# Combat.net
KiCad netlist of a schematic drawn in EAGLE
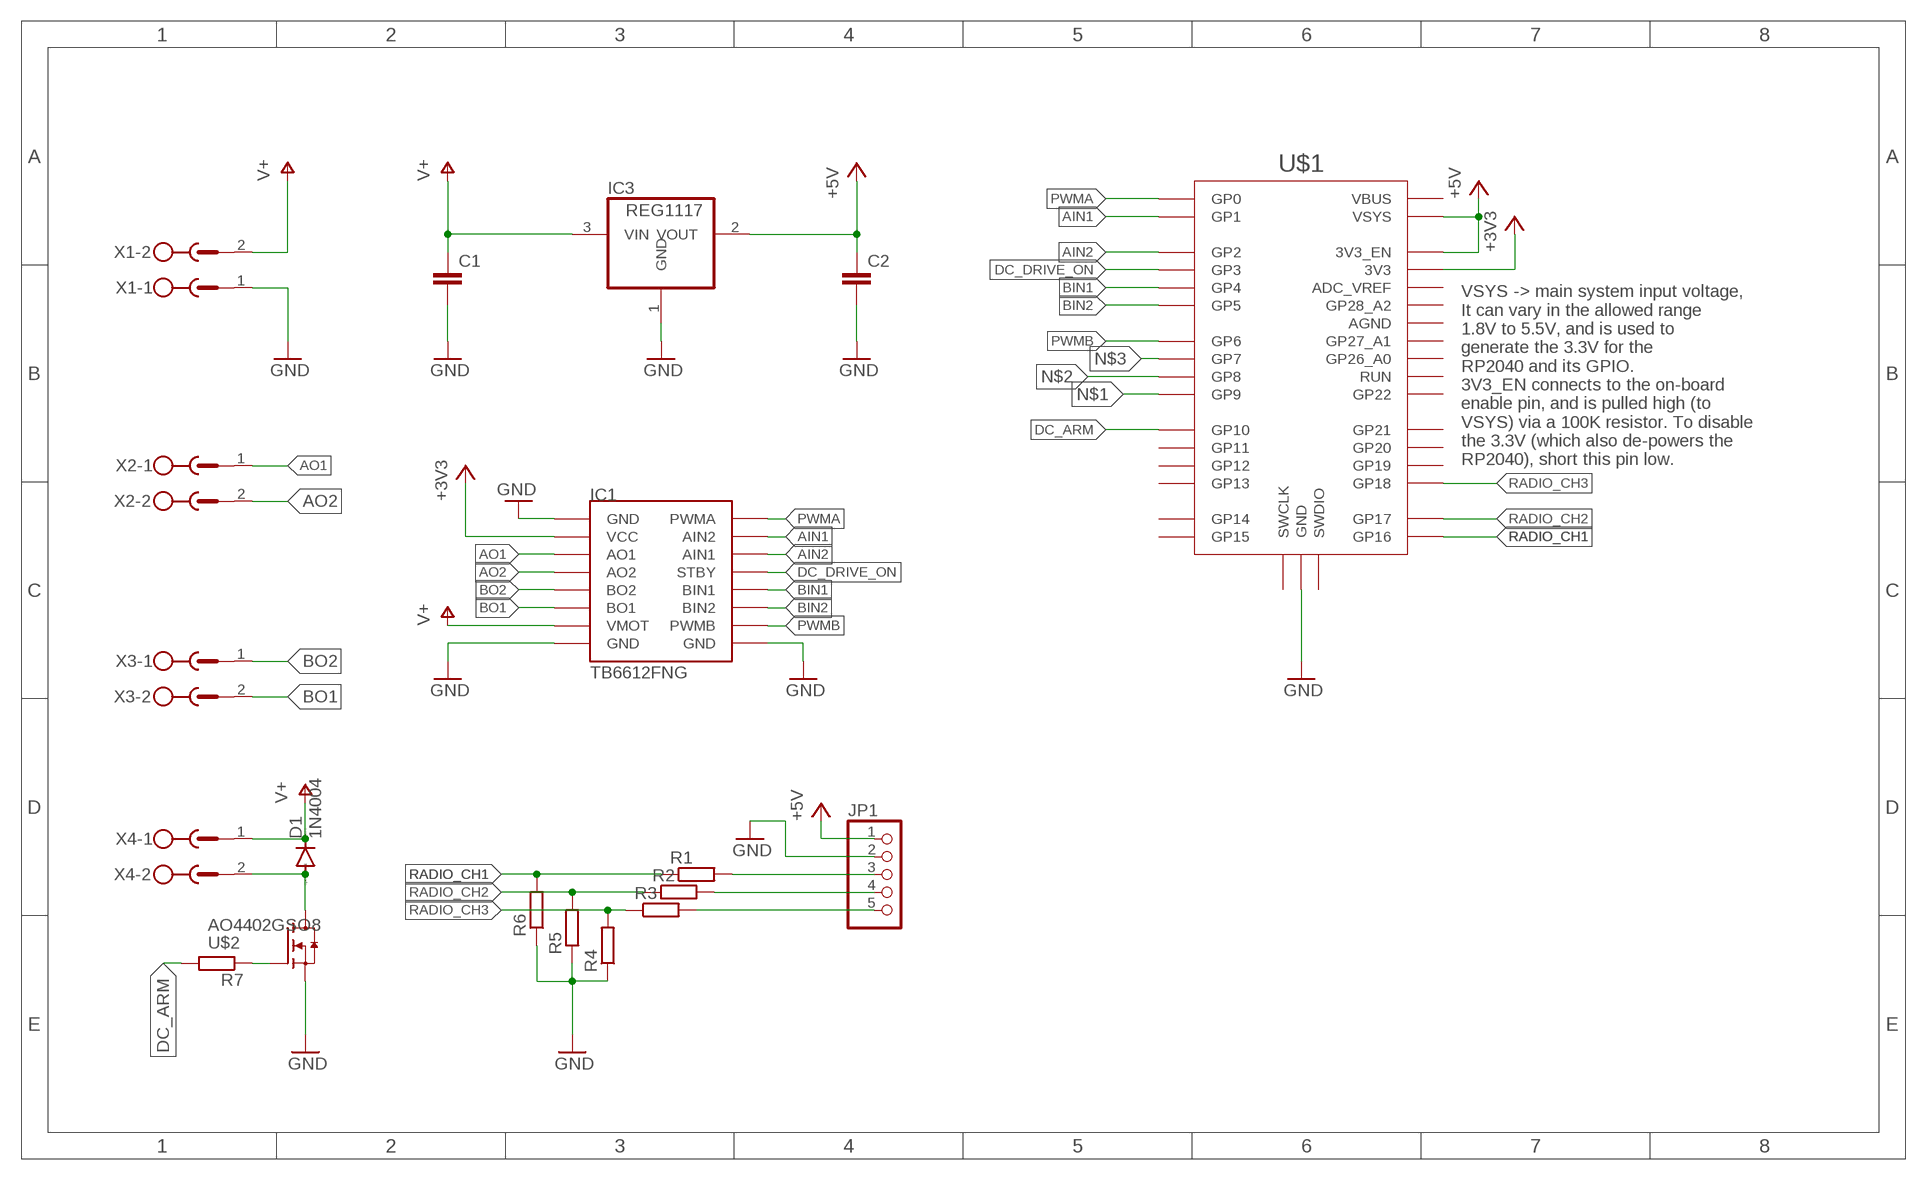
[diagram p0: schematic, sheet 1]

(export (version "E")
  (design (tool "Eeschema 10.0.6"))
  (components
    (comp (ref "C1")
      (value "C-EUC1206")
      (footprint "eagle-import:C1206")
      (libsource (lib "eagle-import") (part "C-EUC1206"))
    )
    (comp (ref "C2")
      (value "C-EUC1206")
      (footprint "eagle-import:C1206")
      (libsource (lib "eagle-import") (part "C-EUC1206"))
    )
    (comp (ref "D1")
      (value "1N4004")
      (footprint "eagle-import:DO41-10")
      (libsource (lib "eagle-import") (part "1N4004"))
    )
    (comp (ref "IC1")
      (value "MODUL_POLOLU")
      (footprint "eagle-import:MODUL_POLOLU")
      (libsource (lib "eagle-import") (part "MODUL_POLOLU"))
    )
    (comp (ref "IC3")
      (value "REG1117")
      (footprint "eagle-import:SOT223")
      (libsource (lib "eagle-import") (part "REG1117"))
    )
    (comp (ref "JP1")
      (value "PINHD-1X5")
      (footprint "eagle-import:1X05")
      (libsource (lib "eagle-import") (part "PINHD-1X5"))
    )
    (comp (ref "R1")
      (value "R-EU_R1206")
      (footprint "eagle-import:R1206")
      (libsource (lib "eagle-import") (part "R-EU_R1206"))
    )
    (comp (ref "R2")
      (value "R-EU_R1206")
      (footprint "eagle-import:R1206")
      (libsource (lib "eagle-import") (part "R-EU_R1206"))
    )
    (comp (ref "R3")
      (value "R-EU_R1206")
      (footprint "eagle-import:R1206")
      (libsource (lib "eagle-import") (part "R-EU_R1206"))
    )
    (comp (ref "R4")
      (value "R-EU_R1206")
      (footprint "eagle-import:R1206")
      (libsource (lib "eagle-import") (part "R-EU_R1206"))
    )
    (comp (ref "R5")
      (value "R-EU_0204/7")
      (footprint "eagle-import:0204_7")
      (libsource (lib "eagle-import") (part "R-EU_0204/7"))
    )
    (comp (ref "R6")
      (value "R-EU_R1206")
      (footprint "eagle-import:R1206")
      (libsource (lib "eagle-import") (part "R-EU_R1206"))
    )
    (comp (ref "R7")
      (value "R-EU_R1206")
      (footprint "eagle-import:R1206")
      (libsource (lib "eagle-import") (part "R-EU_R1206"))
    )
    (comp (ref "U$1")
      (value "RPI_PICO-TH")
      (footprint "eagle-import:RPI_PICO_TH")
      (libsource (lib "eagle-import") (part "RPI_PICO-TH"))
    )
    (comp (ref "U$2")
      (value "AO4402GSO8")
      (footprint "eagle-import:SO8")
      (libsource (lib "eagle-import") (part "AO4402GSO8"))
    )
    (comp (ref "X1")
      (value "MSTBV2")
      (footprint "eagle-import:MSTBV2")
      (libsource (lib "eagle-import") (part "MSTBV2"))
    )
    (comp (ref "X2")
      (value "MSTBV2")
      (footprint "eagle-import:MSTBV2")
      (libsource (lib "eagle-import") (part "MSTBV2"))
    )
    (comp (ref "X3")
      (value "MSTBV2")
      (footprint "eagle-import:MSTBV2")
      (libsource (lib "eagle-import") (part "MSTBV2"))
    )
    (comp (ref "X4")
      (value "MSTBV2")
      (footprint "eagle-import:MSTBV2")
      (libsource (lib "eagle-import") (part "MSTBV2"))
    )
  )
  (nets
    (net (code "1") (name "+3V3") (class "Default")
      (node (ref "IC1") (pin "VCC") (pinfunction "VCC_VCC") (pintype "bidirectional"))
      (node (ref "U$1") (pin "3V3") (pinfunction "3V3_3V3") (pintype "bidirectional"))
    )
    (net (code "2") (name "+5V") (class "Default")
      (node (ref "C2") (pin "1") (pinfunction "1_1") (pintype "passive"))
      (node (ref "IC3") (pin "2") (pinfunction "VOUT_2") (pintype "output"))
      (node (ref "JP1") (pin "1") (pinfunction "1_1") (pintype "passive"))
      (node (ref "U$1") (pin "3V3_EN") (pinfunction "3V3_EN_3V3_EN") (pintype "bidirectional"))
      (node (ref "U$1") (pin "VSYS") (pinfunction "VSYS_VSYS") (pintype "bidirectional"))
    )
    (net (code "3") (name "AIN1") (class "Default")
      (node (ref "IC1") (pin "AIN2") (pinfunction "AIN2_AIN2") (pintype "bidirectional"))
      (node (ref "U$1") (pin "GP1") (pinfunction "GP1_GP1") (pintype "bidirectional"))
    )
    (net (code "4") (name "AIN2") (class "Default")
      (node (ref "IC1") (pin "AIN1") (pinfunction "AIN1_AIN1") (pintype "bidirectional"))
      (node (ref "U$1") (pin "GP2") (pinfunction "GP2_GP2") (pintype "bidirectional"))
    )
    (net (code "5") (name "AO1") (class "Default")
      (node (ref "IC1") (pin "AO1") (pinfunction "AO1_AO1") (pintype "bidirectional"))
      (node (ref "X2") (pin "1") (pinfunction "SK_1") (pintype "passive"))
    )
    (net (code "6") (name "AO2") (class "Default")
      (node (ref "IC1") (pin "A02") (pinfunction "AO2_A02") (pintype "bidirectional"))
      (node (ref "X2") (pin "2") (pinfunction "SK_2") (pintype "passive"))
    )
    (net (code "7") (name "BIN1") (class "Default")
      (node (ref "IC1") (pin "BIN1") (pinfunction "BIN1_BIN1") (pintype "bidirectional"))
      (node (ref "U$1") (pin "GP4") (pinfunction "GP4_GP4") (pintype "bidirectional"))
    )
    (net (code "8") (name "BIN2") (class "Default")
      (node (ref "IC1") (pin "BIN2") (pinfunction "BIN2_BIN2") (pintype "bidirectional"))
      (node (ref "U$1") (pin "GP5") (pinfunction "GP5_GP5") (pintype "bidirectional"))
    )
    (net (code "9") (name "BO1") (class "Default")
      (node (ref "IC1") (pin "BO1") (pinfunction "BO1_BO1") (pintype "bidirectional"))
      (node (ref "X3") (pin "2") (pinfunction "SK_2") (pintype "passive"))
    )
    (net (code "10") (name "BO2") (class "Default")
      (node (ref "IC1") (pin "BO2") (pinfunction "BO2_BO2") (pintype "bidirectional"))
      (node (ref "X3") (pin "1") (pinfunction "SK_1") (pintype "passive"))
    )
    (net (code "11") (name "DC_ARM") (class "Default")
      (node (ref "R7") (pin "2") (pinfunction "2_2") (pintype "passive"))
      (node (ref "U$1") (pin "GP10") (pinfunction "GP10_GP10") (pintype "bidirectional"))
    )
    (net (code "12") (name "DC_DRIVE_ON") (class "Default")
      (node (ref "IC1") (pin "STBY") (pinfunction "STBY_STBY") (pintype "bidirectional"))
      (node (ref "U$1") (pin "GP3") (pinfunction "GP3_GP3") (pintype "bidirectional"))
    )
    (net (code "13") (name "GND") (class "Default")
      (node (ref "C1") (pin "2") (pinfunction "2_2") (pintype "passive"))
      (node (ref "C2") (pin "2") (pinfunction "2_2") (pintype "passive"))
      (node (ref "IC1") (pin "GND1") (pinfunction "GND_GND1") (pintype "bidirectional"))
      (node (ref "IC1") (pin "GND2") (pinfunction "GND_GND2") (pintype "bidirectional"))
      (node (ref "IC1") (pin "GND3") (pinfunction "GND_GND3") (pintype "bidirectional"))
      (node (ref "IC3") (pin "1") (pinfunction "GND_1") (pintype "power_in"))
      (node (ref "JP1") (pin "2") (pinfunction "2_2") (pintype "passive"))
      (node (ref "R4") (pin "1") (pinfunction "1_1") (pintype "passive"))
      (node (ref "R5") (pin "1") (pinfunction "1_1") (pintype "passive"))
      (node (ref "R6") (pin "1") (pinfunction "1_1") (pintype "passive"))
      (node (ref "U$1") (pin "GND@1") (pinfunction "GND_GND@1") (pintype "bidirectional"))
      (node (ref "U$1") (pin "GND@2") (pinfunction "GND_GND@2") (pintype "bidirectional"))
      (node (ref "U$1") (pin "GND@3") (pinfunction "GND_GND@3") (pintype "bidirectional"))
      (node (ref "U$1") (pin "GND@4") (pinfunction "GND_GND@4") (pintype "bidirectional"))
      (node (ref "U$1") (pin "GND@5") (pinfunction "GND_GND@5") (pintype "bidirectional"))
      (node (ref "U$1") (pin "GND@6") (pinfunction "GND_GND@6") (pintype "bidirectional"))
      (node (ref "U$1") (pin "GND@7") (pinfunction "GND_GND@7") (pintype "bidirectional"))
      (node (ref "U$1") (pin "GND@8") (pinfunction "GND_GND@8") (pintype "bidirectional"))
      (node (ref "U$2") (pin "1") (pinfunction "S_1") (pintype "passive"))
      (node (ref "U$2") (pin "2") (pinfunction "S_2") (pintype "passive"))
      (node (ref "U$2") (pin "3") (pinfunction "S_3") (pintype "passive"))
      (node (ref "X1") (pin "1") (pinfunction "SK_1") (pintype "passive"))
    )
    (net (code "14") (name "N$1") (class "Default")
      (node (ref "JP1") (pin "3") (pinfunction "3_3") (pintype "passive"))
      (node (ref "R1") (pin "2") (pinfunction "2_2") (pintype "passive"))
      (node (ref "U$1") (pin "GP9") (pinfunction "GP9_GP9") (pintype "bidirectional"))
    )
    (net (code "15") (name "N$2") (class "Default")
      (node (ref "JP1") (pin "4") (pinfunction "4_4") (pintype "passive"))
      (node (ref "R2") (pin "2") (pinfunction "2_2") (pintype "passive"))
      (node (ref "U$1") (pin "GP8") (pinfunction "GP8_GP8") (pintype "bidirectional"))
    )
    (net (code "16") (name "N$3") (class "Default")
      (node (ref "JP1") (pin "5") (pinfunction "5_5") (pintype "passive"))
      (node (ref "R3") (pin "2") (pinfunction "2_2") (pintype "passive"))
      (node (ref "U$1") (pin "GP7") (pinfunction "GP7_GP7") (pintype "bidirectional"))
    )
    (net (code "17") (name "Net-(U$2-G)") (class "Default")
      (node (ref "R7") (pin "1") (pinfunction "1_1") (pintype "passive"))
      (node (ref "U$2") (pin "4") (pinfunction "G_4") (pintype "passive"))
    )
    (net (code "18") (name "Net-(X4B-SK)") (class "Default")
      (node (ref "D1") (pin "A") (pinfunction "A_A") (pintype "passive"))
      (node (ref "U$2") (pin "5") (pinfunction "D_5") (pintype "passive"))
      (node (ref "U$2") (pin "6") (pinfunction "D_6") (pintype "passive"))
      (node (ref "U$2") (pin "7") (pinfunction "D_7") (pintype "passive"))
      (node (ref "U$2") (pin "8") (pinfunction "D_8") (pintype "passive"))
      (node (ref "X4") (pin "2") (pinfunction "SK_2") (pintype "passive"))
    )
    (net (code "19") (name "PWMA") (class "Default")
      (node (ref "IC1") (pin "PWMA") (pinfunction "PWMA_PWMA") (pintype "bidirectional"))
      (node (ref "U$1") (pin "GP0") (pinfunction "GP0_GP0") (pintype "bidirectional"))
    )
    (net (code "20") (name "PWMB") (class "Default")
      (node (ref "IC1") (pin "PWMB") (pinfunction "PWMB_PWMB") (pintype "bidirectional"))
      (node (ref "U$1") (pin "GP6") (pinfunction "GP6_GP6") (pintype "bidirectional"))
    )
    (net (code "21") (name "RADIO_CH1") (class "Default")
      (node (ref "R1") (pin "1") (pinfunction "1_1") (pintype "passive"))
      (node (ref "R6") (pin "2") (pinfunction "2_2") (pintype "passive"))
      (node (ref "U$1") (pin "GP16") (pinfunction "GP16_GP16") (pintype "bidirectional"))
    )
    (net (code "22") (name "RADIO_CH2") (class "Default")
      (node (ref "R2") (pin "1") (pinfunction "1_1") (pintype "passive"))
      (node (ref "R5") (pin "2") (pinfunction "2_2") (pintype "passive"))
      (node (ref "U$1") (pin "GP17") (pinfunction "GP17_GP17") (pintype "bidirectional"))
    )
    (net (code "23") (name "RADIO_CH3") (class "Default")
      (node (ref "R3") (pin "1") (pinfunction "1_1") (pintype "passive"))
      (node (ref "R4") (pin "2") (pinfunction "2_2") (pintype "passive"))
      (node (ref "U$1") (pin "GP18") (pinfunction "GP18_GP18") (pintype "bidirectional"))
    )
    (net (code "24") (name "V+") (class "Default")
      (node (ref "C1") (pin "1") (pinfunction "1_1") (pintype "passive"))
      (node (ref "D1") (pin "C") (pinfunction "C_C") (pintype "passive"))
      (node (ref "IC1") (pin "VMOT") (pinfunction "VMOT_VMOT") (pintype "bidirectional"))
      (node (ref "IC3") (pin "3") (pinfunction "VIN_3") (pintype "input"))
      (node (ref "X1") (pin "2") (pinfunction "SK_2") (pintype "passive"))
      (node (ref "X4") (pin "1") (pinfunction "SK_1") (pintype "passive"))
    )
    (net (code "25") (name "unconnected-(U$1-PadADC_VREF)") (class "Default")
      (node (ref "U$1") (pin "ADC_VREF") (pinfunction "ADC_VREF_ADC_VREF") (pintype "bidirectional"))
    )
    (net (code "26") (name "unconnected-(U$1-PadAGND)") (class "Default")
      (node (ref "U$1") (pin "AGND") (pinfunction "AGND_AGND") (pintype "bidirectional"))
    )
    (net (code "27") (name "unconnected-(U$1-PadGP11)") (class "Default")
      (node (ref "U$1") (pin "GP11") (pinfunction "GP11_GP11") (pintype "bidirectional"))
    )
    (net (code "28") (name "unconnected-(U$1-PadGP12)") (class "Default")
      (node (ref "U$1") (pin "GP12") (pinfunction "GP12_GP12") (pintype "bidirectional"))
    )
    (net (code "29") (name "unconnected-(U$1-PadGP13)") (class "Default")
      (node (ref "U$1") (pin "GP13") (pinfunction "GP13_GP13") (pintype "bidirectional"))
    )
    (net (code "30") (name "unconnected-(U$1-PadGP14)") (class "Default")
      (node (ref "U$1") (pin "GP14") (pinfunction "GP14_GP14") (pintype "bidirectional"))
    )
    (net (code "31") (name "unconnected-(U$1-PadGP15)") (class "Default")
      (node (ref "U$1") (pin "GP15") (pinfunction "GP15_GP15") (pintype "bidirectional"))
    )
    (net (code "32") (name "unconnected-(U$1-PadGP19)") (class "Default")
      (node (ref "U$1") (pin "GP19") (pinfunction "GP19_GP19") (pintype "bidirectional"))
    )
    (net (code "33") (name "unconnected-(U$1-PadGP20)") (class "Default")
      (node (ref "U$1") (pin "GP20") (pinfunction "GP20_GP20") (pintype "bidirectional"))
    )
    (net (code "34") (name "unconnected-(U$1-PadGP21)") (class "Default")
      (node (ref "U$1") (pin "GP21") (pinfunction "GP21_GP21") (pintype "bidirectional"))
    )
    (net (code "35") (name "unconnected-(U$1-PadGP22)") (class "Default")
      (node (ref "U$1") (pin "GP22") (pinfunction "GP22_GP22") (pintype "bidirectional"))
    )
    (net (code "36") (name "unconnected-(U$1-PadGP26_A0)") (class "Default")
      (node (ref "U$1") (pin "GP26_A0") (pinfunction "GP26_A0_GP26_A0") (pintype "bidirectional"))
    )
    (net (code "37") (name "unconnected-(U$1-PadGP27_A1)") (class "Default")
      (node (ref "U$1") (pin "GP27_A1") (pinfunction "GP27_A1_GP27_A1") (pintype "bidirectional"))
    )
    (net (code "38") (name "unconnected-(U$1-PadGP28_A2)") (class "Default")
      (node (ref "U$1") (pin "GP28_A2") (pinfunction "GP28_A2_GP28_A2") (pintype "bidirectional"))
    )
    (net (code "39") (name "unconnected-(U$1-PadRUN)") (class "Default")
      (node (ref "U$1") (pin "RUN") (pinfunction "RUN_RUN") (pintype "bidirectional"))
    )
    (net (code "40") (name "unconnected-(U$1-PadSWCLK)") (class "Default")
      (node (ref "U$1") (pin "SWCLK") (pinfunction "SWCLK_SWCLK") (pintype "bidirectional"))
    )
    (net (code "41") (name "unconnected-(U$1-PadSWDIO)") (class "Default")
      (node (ref "U$1") (pin "SWDIO") (pinfunction "SWDIO_SWDIO") (pintype "bidirectional"))
    )
    (net (code "42") (name "unconnected-(U$1-PadVBUS)") (class "Default")
      (node (ref "U$1") (pin "VBUS") (pinfunction "VBUS_VBUS") (pintype "bidirectional"))
    )
  )
)
